# cutdown.net
KiCad netlist of a schematic drawn in EAGLE
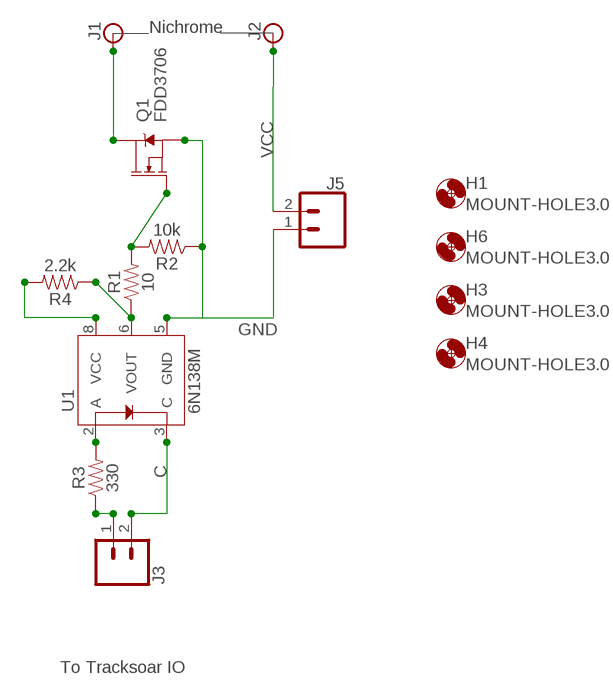
[diagram p0: schematic, sheet 1]

(export (version "E")
  (design (tool "Eeschema 10.0.6"))
  (components
    (comp (ref "H1")
      (value "MOUNT-HOLE3.0")
      (footprint "eagle-import:3,0")
      (libsource (lib "eagle-import") (part "MOUNT-HOLE3.0"))
    )
    (comp (ref "H3")
      (value "MOUNT-HOLE3.0")
      (footprint "eagle-import:3,0")
      (libsource (lib "eagle-import") (part "MOUNT-HOLE3.0"))
    )
    (comp (ref "H4")
      (value "MOUNT-HOLE3.0")
      (footprint "eagle-import:3,0")
      (libsource (lib "eagle-import") (part "MOUNT-HOLE3.0"))
    )
    (comp (ref "H6")
      (value "MOUNT-HOLE3.0")
      (footprint "eagle-import:3,0")
      (libsource (lib "eagle-import") (part "MOUNT-HOLE3.0"))
    )
    (comp (ref "J1")
      (value "BANANA_CONN")
      (footprint "eagle-import:BANANA_CONN")
      (libsource (lib "eagle-import") (part "BANANA_CONN"))
    )
    (comp (ref "J2")
      (value "BANANA_CONN")
      (footprint "eagle-import:BANANA_CONN")
      (libsource (lib "eagle-import") (part "BANANA_CONN"))
    )
    (comp (ref "J3")
      (value "CONN_02PTH3")
      (footprint "eagle-import:1X02_LONGPADS")
      (libsource (lib "eagle-import") (part "CONN_02PTH3"))
    )
    (comp (ref "J5")
      (value "CONN_02PTH3")
      (footprint "eagle-import:1X02_LONGPADS")
      (libsource (lib "eagle-import") (part "CONN_02PTH3"))
    )
    (comp (ref "Q1")
      (value "FDD3706")
      (footprint "eagle-import:DPAK")
      (libsource (lib "eagle-import") (part "MOSFET-NCH-FDD8780"))
    )
    (comp (ref "R1")
      (value "10")
      (footprint "eagle-import:0603")
      (libsource (lib "eagle-import") (part "10OHM-0603-1/10W-1%"))
    )
    (comp (ref "R2")
      (value "10k")
      (footprint "eagle-import:0603")
      (libsource (lib "eagle-import") (part "10KOHM-0603-1/10W-1%"))
    )
    (comp (ref "R3")
      (value "330")
      (footprint "eagle-import:0603")
      (libsource (lib "eagle-import") (part "10OHM-0603-1/10W-1%"))
    )
    (comp (ref "R4")
      (value "2.2k")
      (footprint "eagle-import:0603")
      (libsource (lib "eagle-import") (part "10OHM-0603-1/10W-1%"))
    )
    (comp (ref "U1")
      (value "6N138M")
      (footprint "eagle-import:8-SMD")
      (libsource (lib "eagle-import") (part "OPTO_DARL_6N138S"))
    )
  )
  (nets
    (net (code "1") (name "/C") (class "Default")
      (node (ref "J3") (pin "2") (pinfunction "2_2") (pintype "passive"))
      (node (ref "U1") (pin "3") (pinfunction "C_3") (pintype "bidirectional"))
    )
    (net (code "2") (name "/GND") (class "Default")
      (node (ref "J5") (pin "1") (pinfunction "1_1") (pintype "passive"))
      (node (ref "Q1") (pin "3") (pinfunction "S_3") (pintype "bidirectional"))
      (node (ref "R2") (pin "1") (pinfunction "1_1") (pintype "passive"))
      (node (ref "U1") (pin "5") (pinfunction "GND_5") (pintype "bidirectional"))
    )
    (net (code "3") (name "/VCC") (class "Default")
      (node (ref "J2") (pin "P$1") (pinfunction "1_P$1") (pintype "passive"))
      (node (ref "J5") (pin "2") (pinfunction "2_2") (pintype "passive"))
    )
    (net (code "4") (name "Net-(J1-1)") (class "Default")
      (node (ref "J1") (pin "P$1") (pinfunction "1_P$1") (pintype "passive"))
      (node (ref "Q1") (pin "4") (pinfunction "D_4") (pintype "bidirectional"))
    )
    (net (code "5") (name "Net-(J3-Pad1)") (class "Default")
      (node (ref "J3") (pin "1") (pinfunction "1_1") (pintype "passive"))
      (node (ref "R3") (pin "1") (pinfunction "1_1") (pintype "passive"))
    )
    (net (code "6") (name "Net-(Q1-G)") (class "Default")
      (node (ref "Q1") (pin "1") (pinfunction "G_1") (pintype "bidirectional"))
      (node (ref "R1") (pin "2") (pinfunction "2_2") (pintype "passive"))
      (node (ref "R2") (pin "2") (pinfunction "2_2") (pintype "passive"))
    )
    (net (code "7") (name "Net-(U1-A)") (class "Default")
      (node (ref "R3") (pin "2") (pinfunction "2_2") (pintype "passive"))
      (node (ref "U1") (pin "2") (pinfunction "A_2") (pintype "bidirectional"))
    )
    (net (code "8") (name "Net-(U1-VCC)") (class "Default")
      (node (ref "R4") (pin "2") (pinfunction "2_2") (pintype "passive"))
      (node (ref "U1") (pin "8") (pinfunction "VCC_8") (pintype "bidirectional"))
    )
    (net (code "9") (name "Net-(U1-VOUT)") (class "Default")
      (node (ref "R1") (pin "1") (pinfunction "1_1") (pintype "passive"))
      (node (ref "R4") (pin "1") (pinfunction "1_1") (pintype "passive"))
      (node (ref "U1") (pin "6") (pinfunction "VOUT_6") (pintype "bidirectional"))
    )
  )
)
